# ArduinoProMiniLEDdriver.net
KiCad netlist of a schematic drawn in EAGLE
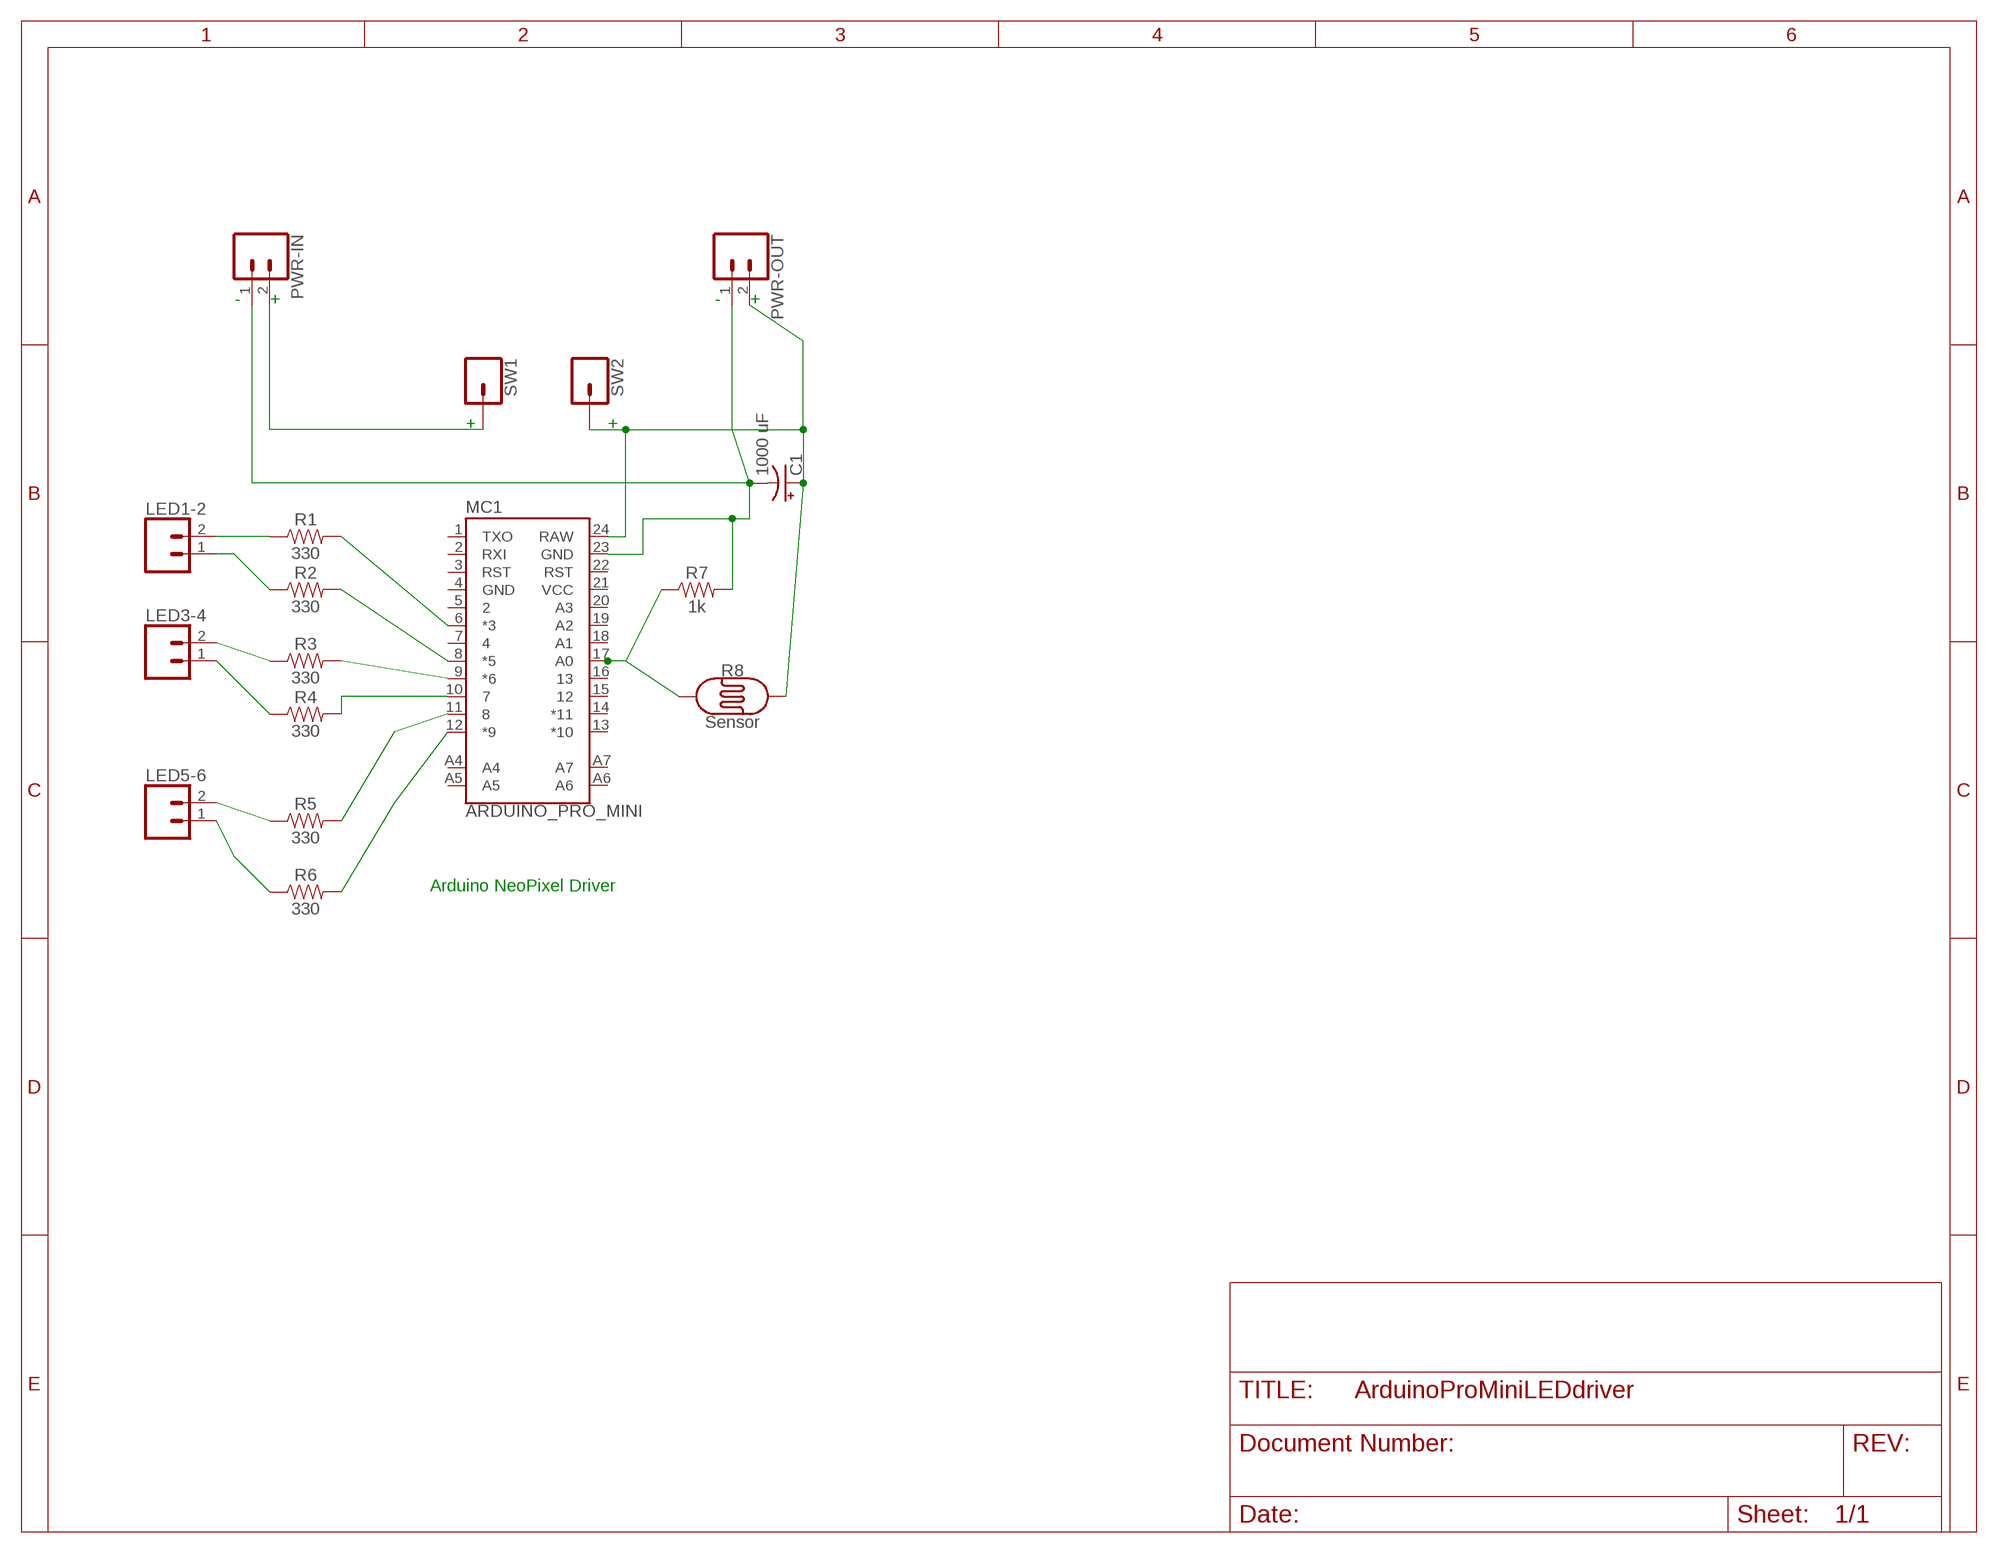
[diagram p0: schematic, sheet 1]

(export (version "E")
  (design (tool "Eeschema 10.0.6"))
  (components
    (comp (ref "C1")
      (value "1000 uF")
      (footprint "eagle-import:CPOL-RADIAL-5MM-10MM")
      (libsource (lib "eagle-import") (part "1000UF-RADIAL-5MM-25V-20%"))
    )
    (comp (ref "LED1-2")
      (value "CONN_025MM")
      (footprint "eagle-import:SCREWTERMINAL-5MM-2")
      (libsource (lib "eagle-import") (part "CONN_025MM"))
    )
    (comp (ref "LED3-4")
      (value "CONN_025MM")
      (footprint "eagle-import:SCREWTERMINAL-5MM-2")
      (libsource (lib "eagle-import") (part "CONN_025MM"))
    )
    (comp (ref "LED5-6")
      (value "CONN_025MM")
      (footprint "eagle-import:SCREWTERMINAL-5MM-2")
      (libsource (lib "eagle-import") (part "CONN_025MM"))
    )
    (comp (ref "MC1")
      (value "ARDUINO_PRO_MINI")
      (footprint "eagle-import:ARDUINO_PRO_MINI")
      (libsource (lib "eagle-import") (part "ARDUINO_PRO_MINI"))
    )
    (comp (ref "PWR-IN")
      (value "CONN_025MM")
      (footprint "eagle-import:SCREWTERMINAL-5MM-2")
      (libsource (lib "eagle-import") (part "CONN_025MM"))
    )
    (comp (ref "PWR-OUT")
      (value "CONN_025MM")
      (footprint "eagle-import:SCREWTERMINAL-5MM-2")
      (libsource (lib "eagle-import") (part "CONN_025MM"))
    )
    (comp (ref "R1")
      (value "330")
      (footprint "eagle-import:AXIAL-0.3")
      (libsource (lib "eagle-import") (part "330OHM-HORIZ-1/10W-5%"))
    )
    (comp (ref "R2")
      (value "330")
      (footprint "eagle-import:AXIAL-0.3")
      (libsource (lib "eagle-import") (part "330OHM-HORIZ-1/10W-5%"))
    )
    (comp (ref "R3")
      (value "330")
      (footprint "eagle-import:AXIAL-0.3")
      (libsource (lib "eagle-import") (part "330OHM-HORIZ-1/10W-5%"))
    )
    (comp (ref "R4")
      (value "330")
      (footprint "eagle-import:AXIAL-0.3")
      (libsource (lib "eagle-import") (part "330OHM-HORIZ-1/10W-5%"))
    )
    (comp (ref "R5")
      (value "330")
      (footprint "eagle-import:AXIAL-0.3")
      (libsource (lib "eagle-import") (part "330OHM-HORIZ-1/10W-5%"))
    )
    (comp (ref "R6")
      (value "330")
      (footprint "eagle-import:AXIAL-0.3")
      (libsource (lib "eagle-import") (part "330OHM-HORIZ-1/10W-5%"))
    )
    (comp (ref "R7")
      (value "1k")
      (footprint "eagle-import:AXIAL-0.3")
      (libsource (lib "eagle-import") (part "1KOHM-HORIZ-1/4W-1%"))
    )
    (comp (ref "R8")
      (value "Sensor")
      (footprint "eagle-import:PHOTOCELL")
      (libsource (lib "eagle-import") (part "PHOTOCELLPTH"))
    )
    (comp (ref "SW1")
      (value "CONN_01")
      (footprint "eagle-import:1X01")
      (libsource (lib "eagle-import") (part "CONN_01"))
    )
    (comp (ref "SW2")
      (value "CONN_01")
      (footprint "eagle-import:1X01")
      (libsource (lib "eagle-import") (part "CONN_01"))
    )
  )
  (nets
    (net (code "1") (name "/GND") (class "Default")
      (node (ref "MC1") (pin "4") (pinfunction "GND_4") (pintype "power_in"))
    )
    (net (code "2") (name "/VCC") (class "Default")
      (node (ref "MC1") (pin "21") (pinfunction "VCC_21") (pintype "power_in"))
    )
    (net (code "3") (name "Net-(MC1-*3)") (class "Default")
      (node (ref "MC1") (pin "6") (pinfunction "*3_6") (pintype "bidirectional"))
      (node (ref "R1") (pin "P$2") (pinfunction "2_P$2") (pintype "passive"))
    )
    (net (code "4") (name "Net-(MC1-*5)") (class "Default")
      (node (ref "MC1") (pin "8") (pinfunction "*5_8") (pintype "bidirectional"))
      (node (ref "R2") (pin "P$2") (pinfunction "2_P$2") (pintype "passive"))
    )
    (net (code "5") (name "Net-(MC1-*6)") (class "Default")
      (node (ref "MC1") (pin "9") (pinfunction "*6_9") (pintype "bidirectional"))
      (node (ref "R3") (pin "P$2") (pinfunction "2_P$2") (pintype "passive"))
    )
    (net (code "6") (name "Net-(MC1-*9)") (class "Default")
      (node (ref "MC1") (pin "12") (pinfunction "*9_12") (pintype "bidirectional"))
      (node (ref "R6") (pin "P$2") (pinfunction "2_P$2") (pintype "passive"))
    )
    (net (code "7") (name "Net-(MC1-7)") (class "Default")
      (node (ref "MC1") (pin "10") (pinfunction "7_10") (pintype "bidirectional"))
      (node (ref "R4") (pin "P$2") (pinfunction "2_P$2") (pintype "passive"))
    )
    (net (code "8") (name "Net-(MC1-8)") (class "Default")
      (node (ref "MC1") (pin "11") (pinfunction "8_11") (pintype "bidirectional"))
      (node (ref "R5") (pin "P$2") (pinfunction "2_P$2") (pintype "passive"))
    )
    (net (code "9") (name "Net-(MC1-A0)") (class "Default")
      (node (ref "MC1") (pin "17") (pinfunction "A0_17") (pintype "bidirectional"))
      (node (ref "R7") (pin "P$1") (pinfunction "1_P$1") (pintype "passive"))
      (node (ref "R8") (pin "1") (pinfunction "P$1_1") (pintype "bidirectional"))
    )
    (net (code "10") (name "Net-(MC1-RAW)") (class "Default")
      (node (ref "C1") (pin "+") (pinfunction "+_+") (pintype "passive"))
      (node (ref "MC1") (pin "24") (pinfunction "RAW_24") (pintype "power_in"))
      (node (ref "PWR-OUT") (pin "2") (pinfunction "2_2") (pintype "passive"))
      (node (ref "R8") (pin "2") (pinfunction "P$2_2") (pintype "bidirectional"))
      (node (ref "SW2") (pin "1") (pinfunction "1_1") (pintype "passive"))
    )
    (net (code "11") (name "Net-(PWR-IN-Pad2)") (class "Default")
      (node (ref "PWR-IN") (pin "2") (pinfunction "2_2") (pintype "passive"))
      (node (ref "SW1") (pin "1") (pinfunction "1_1") (pintype "passive"))
    )
    (net (code "12") (name "Net-(R1-1)") (class "Default")
      (node (ref "LED1-2") (pin "2") (pinfunction "2_2") (pintype "passive"))
      (node (ref "R1") (pin "P$1") (pinfunction "1_P$1") (pintype "passive"))
    )
    (net (code "13") (name "Net-(R2-1)") (class "Default")
      (node (ref "LED1-2") (pin "1") (pinfunction "1_1") (pintype "passive"))
      (node (ref "R2") (pin "P$1") (pinfunction "1_P$1") (pintype "passive"))
    )
    (net (code "14") (name "Net-(R3-1)") (class "Default")
      (node (ref "LED3-4") (pin "2") (pinfunction "2_2") (pintype "passive"))
      (node (ref "R3") (pin "P$1") (pinfunction "1_P$1") (pintype "passive"))
    )
    (net (code "15") (name "Net-(R4-1)") (class "Default")
      (node (ref "LED3-4") (pin "1") (pinfunction "1_1") (pintype "passive"))
      (node (ref "R4") (pin "P$1") (pinfunction "1_P$1") (pintype "passive"))
    )
    (net (code "16") (name "Net-(R5-1)") (class "Default")
      (node (ref "LED5-6") (pin "2") (pinfunction "2_2") (pintype "passive"))
      (node (ref "R5") (pin "P$1") (pinfunction "1_P$1") (pintype "passive"))
    )
    (net (code "17") (name "Net-(R6-1)") (class "Default")
      (node (ref "LED5-6") (pin "1") (pinfunction "1_1") (pintype "passive"))
      (node (ref "R6") (pin "P$1") (pinfunction "1_P$1") (pintype "passive"))
    )
    (net (code "18") (name "Net-(R7-2)") (class "Default")
      (node (ref "C1") (pin "-") (pinfunction "-_-") (pintype "passive"))
      (node (ref "MC1") (pin "23") (pinfunction "GND_23") (pintype "power_in"))
      (node (ref "PWR-IN") (pin "1") (pinfunction "1_1") (pintype "passive"))
      (node (ref "PWR-OUT") (pin "1") (pinfunction "1_1") (pintype "passive"))
      (node (ref "R7") (pin "P$2") (pinfunction "2_P$2") (pintype "passive"))
    )
    (net (code "19") (name "unconnected-(MC1-*10-Pad13)") (class "Default")
      (node (ref "MC1") (pin "13") (pinfunction "*10_13") (pintype "bidirectional"))
    )
    (net (code "20") (name "unconnected-(MC1-*11-Pad14)") (class "Default")
      (node (ref "MC1") (pin "14") (pinfunction "*11_14") (pintype "bidirectional"))
    )
    (net (code "21") (name "unconnected-(MC1-2-Pad5)") (class "Default")
      (node (ref "MC1") (pin "5") (pinfunction "2_5") (pintype "bidirectional"))
    )
    (net (code "22") (name "unconnected-(MC1-4-Pad7)") (class "Default")
      (node (ref "MC1") (pin "7") (pinfunction "4_7") (pintype "bidirectional"))
    )
    (net (code "23") (name "unconnected-(MC1-12-Pad15)") (class "Default")
      (node (ref "MC1") (pin "15") (pinfunction "12_15") (pintype "bidirectional"))
    )
    (net (code "24") (name "unconnected-(MC1-13-Pad16)") (class "Default")
      (node (ref "MC1") (pin "16") (pinfunction "13_16") (pintype "bidirectional"))
    )
    (net (code "25") (name "unconnected-(MC1-A1-Pad18)") (class "Default")
      (node (ref "MC1") (pin "18") (pinfunction "A1_18") (pintype "bidirectional"))
    )
    (net (code "26") (name "unconnected-(MC1-A2-Pad19)") (class "Default")
      (node (ref "MC1") (pin "19") (pinfunction "A2_19") (pintype "bidirectional"))
    )
    (net (code "27") (name "unconnected-(MC1-A3-Pad20)") (class "Default")
      (node (ref "MC1") (pin "20") (pinfunction "A3_20") (pintype "bidirectional"))
    )
    (net (code "28") (name "unconnected-(MC1-PadA4)") (class "Default")
      (node (ref "MC1") (pin "A4") (pinfunction "A4_A4") (pintype "bidirectional"))
    )
    (net (code "29") (name "unconnected-(MC1-PadA5)") (class "Default")
      (node (ref "MC1") (pin "A5") (pinfunction "A5_A5") (pintype "bidirectional"))
    )
    (net (code "30") (name "unconnected-(MC1-PadA6)") (class "Default")
      (node (ref "MC1") (pin "A6") (pinfunction "A6_A6") (pintype "bidirectional"))
    )
    (net (code "31") (name "unconnected-(MC1-PadA7)") (class "Default")
      (node (ref "MC1") (pin "A7") (pinfunction "A7_A7") (pintype "bidirectional"))
    )
    (net (code "32") (name "unconnected-(MC1-RST-Pad3)") (class "Default")
      (node (ref "MC1") (pin "3") (pinfunction "RST_3") (pintype "bidirectional"))
    )
    (net (code "33") (name "unconnected-(MC1-RST-Pad22)") (class "Default")
      (node (ref "MC1") (pin "22") (pinfunction "RST_22") (pintype "bidirectional"))
    )
    (net (code "34") (name "unconnected-(MC1-RXI-Pad2)") (class "Default")
      (node (ref "MC1") (pin "2") (pinfunction "RXI_2") (pintype "bidirectional"))
    )
    (net (code "35") (name "unconnected-(MC1-TXO-Pad1)") (class "Default")
      (node (ref "MC1") (pin "1") (pinfunction "TXO_1") (pintype "bidirectional"))
    )
  )
)
